# cluster.net
KiCad netlist of a schematic drawn in EAGLE
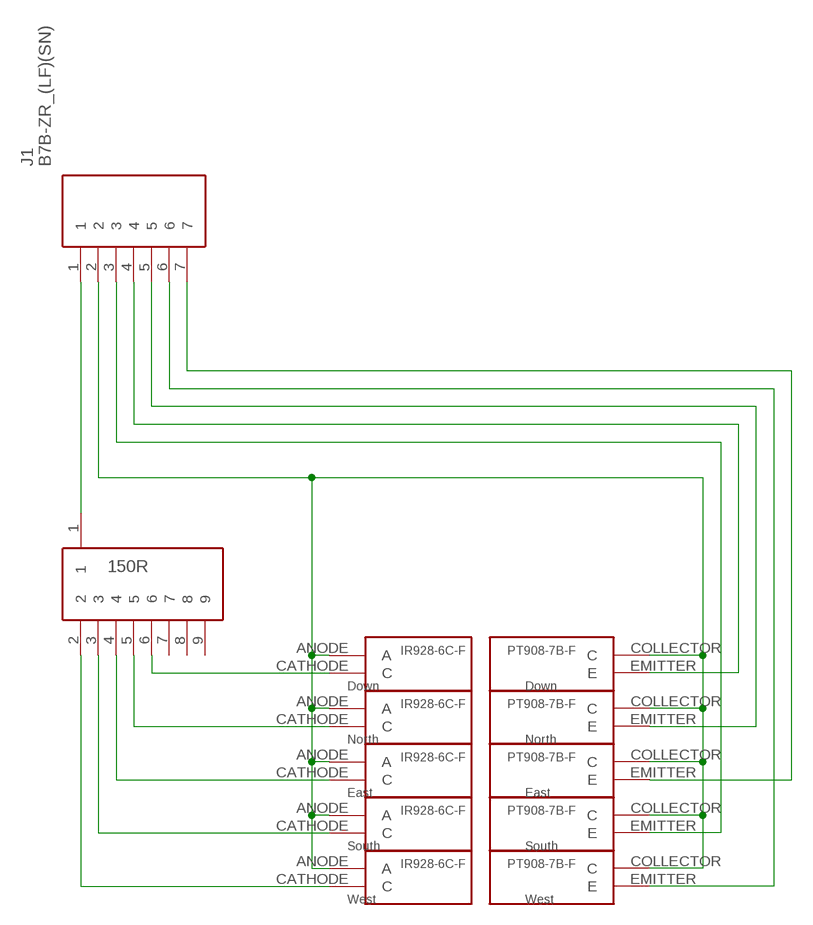
[diagram p0: schematic, sheet 1]

(export (version "E")
  (design (tool "Eeschema 10.0.6"))
  (components
    (comp (ref "150R")
      (value "150R")
      (footprint "eagle-import:9PIN-RESISTOR-NETWORK")
      (libsource (lib "eagle-import") (part "9PIN-RESISTOR-NETWORK9PIN-RESISTOR-NETWORK"))
    )
    (comp (ref "J1")
      (value "B7B-ZR_(LF)(SN)")
      (footprint "eagle-import:SHDR7W50P0X150_1X7_1200X350X45")
      (fields
        (field (name "MANUFACTURER_PART_NUMBER") "B7B-ZR (LF)(SN)")
        (field (name "RS_PART_NUMBER") "7620828")
      )
      (libsource (lib "eagle-import") (part "B7B-ZR_(LF)(SN)"))
    )
    (comp (ref "LED1")
      (value "Down")
      (footprint "eagle-import:IR928-6C-F")
      (libsource (lib "eagle-import") (part "IR928-6C-F"))
    )
    (comp (ref "LED2")
      (value "North")
      (footprint "eagle-import:IR928-6C-F")
      (libsource (lib "eagle-import") (part "IR928-6C-F"))
    )
    (comp (ref "LED3")
      (value "East")
      (footprint "eagle-import:IR928-6C-F")
      (libsource (lib "eagle-import") (part "IR928-6C-F"))
    )
    (comp (ref "LED4")
      (value "South")
      (footprint "eagle-import:IR928-6C-F")
      (libsource (lib "eagle-import") (part "IR928-6C-F"))
    )
    (comp (ref "LED5")
      (value "West")
      (footprint "eagle-import:IR928-6C-F")
      (libsource (lib "eagle-import") (part "IR928-6C-F"))
    )
    (comp (ref "PT1")
      (value "Down")
      (footprint "eagle-import:PT908-7B-F")
      (libsource (lib "eagle-import") (part "PT908-7B-F"))
    )
    (comp (ref "PT2")
      (value "North")
      (footprint "eagle-import:PT908-7B-F")
      (libsource (lib "eagle-import") (part "PT908-7B-F"))
    )
    (comp (ref "PT3")
      (value "East")
      (footprint "eagle-import:PT908-7B-F")
      (libsource (lib "eagle-import") (part "PT908-7B-F"))
    )
    (comp (ref "PT4")
      (value "South")
      (footprint "eagle-import:PT908-7B-F")
      (libsource (lib "eagle-import") (part "PT908-7B-F"))
    )
    (comp (ref "PT5")
      (value "West")
      (footprint "eagle-import:PT908-7B-F")
      (libsource (lib "eagle-import") (part "PT908-7B-F"))
    )
  )
  (nets
    (net (code "1") (name "Net-(150R-Pad1)") (class "Default")
      (node (ref "150R") (pin "1") (pinfunction "1_1") (pintype "bidirectional"))
      (node (ref "J1") (pin "1") (pinfunction "1_1") (pintype "bidirectional"))
    )
    (net (code "2") (name "Net-(LED1-A)") (class "Default")
      (node (ref "J1") (pin "2") (pinfunction "2_2") (pintype "bidirectional"))
      (node (ref "LED1") (pin "ANODE") (pinfunction "A_ANODE") (pintype "input"))
      (node (ref "LED2") (pin "ANODE") (pinfunction "A_ANODE") (pintype "input"))
      (node (ref "LED3") (pin "ANODE") (pinfunction "A_ANODE") (pintype "input"))
      (node (ref "LED4") (pin "ANODE") (pinfunction "A_ANODE") (pintype "input"))
      (node (ref "LED5") (pin "ANODE") (pinfunction "A_ANODE") (pintype "input"))
      (node (ref "PT1") (pin "COLLECTOR") (pinfunction "C_COLLECTOR") (pintype "input"))
      (node (ref "PT2") (pin "COLLECTOR") (pinfunction "C_COLLECTOR") (pintype "input"))
      (node (ref "PT3") (pin "COLLECTOR") (pinfunction "C_COLLECTOR") (pintype "input"))
      (node (ref "PT4") (pin "COLLECTOR") (pinfunction "C_COLLECTOR") (pintype "input"))
      (node (ref "PT5") (pin "COLLECTOR") (pinfunction "C_COLLECTOR") (pintype "input"))
    )
    (net (code "3") (name "Net-(LED1-C)") (class "Default")
      (node (ref "150R") (pin "6") (pinfunction "6_6") (pintype "bidirectional"))
      (node (ref "LED1") (pin "CATHODE") (pinfunction "C_CATHODE") (pintype "output"))
    )
    (net (code "4") (name "Net-(LED2-C)") (class "Default")
      (node (ref "150R") (pin "5") (pinfunction "5_5") (pintype "bidirectional"))
      (node (ref "LED2") (pin "CATHODE") (pinfunction "C_CATHODE") (pintype "output"))
    )
    (net (code "5") (name "Net-(LED3-C)") (class "Default")
      (node (ref "150R") (pin "4") (pinfunction "4_4") (pintype "bidirectional"))
      (node (ref "LED3") (pin "CATHODE") (pinfunction "C_CATHODE") (pintype "output"))
    )
    (net (code "6") (name "Net-(LED4-C)") (class "Default")
      (node (ref "150R") (pin "3") (pinfunction "3_3") (pintype "bidirectional"))
      (node (ref "LED4") (pin "CATHODE") (pinfunction "C_CATHODE") (pintype "output"))
    )
    (net (code "7") (name "Net-(LED5-C)") (class "Default")
      (node (ref "150R") (pin "2") (pinfunction "2_2") (pintype "bidirectional"))
      (node (ref "LED5") (pin "CATHODE") (pinfunction "C_CATHODE") (pintype "output"))
    )
    (net (code "8") (name "Net-(PT1-E)") (class "Default")
      (node (ref "J1") (pin "4") (pinfunction "4_4") (pintype "bidirectional"))
      (node (ref "PT1") (pin "EMITTER") (pinfunction "E_EMITTER") (pintype "output"))
    )
    (net (code "9") (name "Net-(PT2-E)") (class "Default")
      (node (ref "J1") (pin "5") (pinfunction "5_5") (pintype "bidirectional"))
      (node (ref "PT2") (pin "EMITTER") (pinfunction "E_EMITTER") (pintype "output"))
    )
    (net (code "10") (name "Net-(PT3-E)") (class "Default")
      (node (ref "J1") (pin "7") (pinfunction "7_7") (pintype "bidirectional"))
      (node (ref "PT3") (pin "EMITTER") (pinfunction "E_EMITTER") (pintype "output"))
    )
    (net (code "11") (name "Net-(PT4-E)") (class "Default")
      (node (ref "J1") (pin "3") (pinfunction "3_3") (pintype "bidirectional"))
      (node (ref "PT4") (pin "EMITTER") (pinfunction "E_EMITTER") (pintype "output"))
    )
    (net (code "12") (name "Net-(PT5-E)") (class "Default")
      (node (ref "J1") (pin "6") (pinfunction "6_6") (pintype "bidirectional"))
      (node (ref "PT5") (pin "EMITTER") (pinfunction "E_EMITTER") (pintype "output"))
    )
    (net (code "13") (name "unconnected-(150R-Pad7)") (class "Default")
      (node (ref "150R") (pin "7") (pinfunction "7_7") (pintype "bidirectional"))
    )
    (net (code "14") (name "unconnected-(150R-Pad8)") (class "Default")
      (node (ref "150R") (pin "8") (pinfunction "8_8") (pintype "bidirectional"))
    )
    (net (code "15") (name "unconnected-(150R-Pad9)") (class "Default")
      (node (ref "150R") (pin "9") (pinfunction "9_9") (pintype "bidirectional"))
    )
  )
)
